# VISCAShield.net
KiCad netlist of a schematic drawn in EAGLE
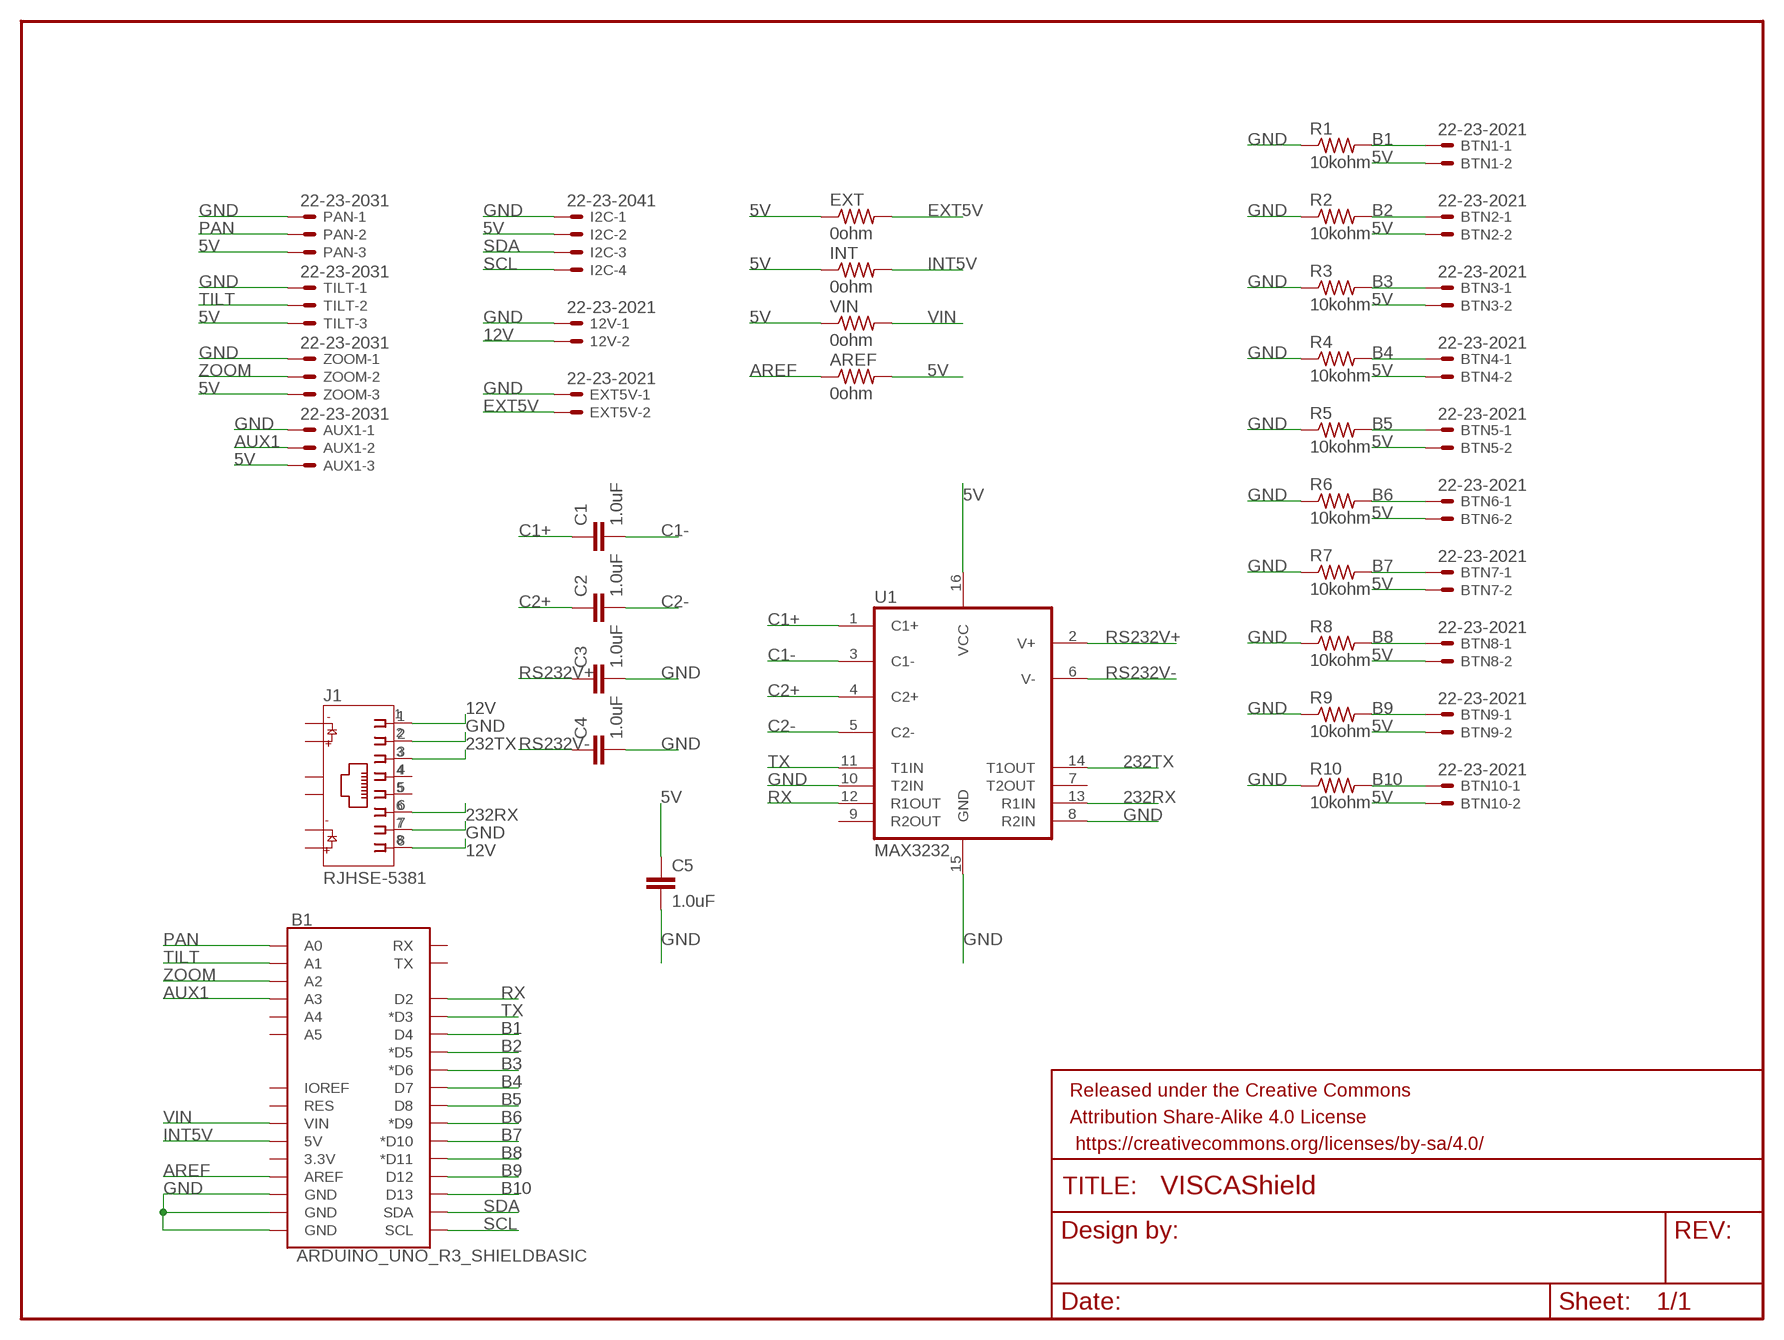
[diagram p0: schematic, sheet 1]

(export (version "E")
  (design (tool "Eeschema 10.0.6"))
  (components
    (comp (ref "12V")
      (value "22-23-2021")
      (footprint "eagle-import:22-23-2021")
      (fields (field (name "MF") "MOLEX"))
      (libsource (lib "eagle-import") (part "22-23-2021"))
    )
    (comp (ref "AREF")
      (value "0ohm")
      (footprint "eagle-import:0204V")
      (libsource (lib "eagle-import") (part "R-US_0204/2V"))
    )
    (comp (ref "AUX1")
      (value "22-23-2031")
      (footprint "eagle-import:22-23-2031")
      (fields (field (name "MF") "MOLEX"))
      (libsource (lib "eagle-import") (part "22-23-2031"))
    )
    (comp (ref "B1")
      (value "ARDUINO_UNO_R3_SHIELDBASIC")
      (footprint "eagle-import:UNO_R3_SHIELD")
      (libsource (lib "eagle-import") (part "ARDUINO_UNO_R3_SHIELDBASIC"))
    )
    (comp (ref "BTN1")
      (value "22-23-2021")
      (footprint "eagle-import:22-23-2021")
      (fields (field (name "MF") "MOLEX"))
      (libsource (lib "eagle-import") (part "22-23-2021"))
    )
    (comp (ref "BTN2")
      (value "22-23-2021")
      (footprint "eagle-import:22-23-2021")
      (fields (field (name "MF") "MOLEX"))
      (libsource (lib "eagle-import") (part "22-23-2021"))
    )
    (comp (ref "BTN3")
      (value "22-23-2021")
      (footprint "eagle-import:22-23-2021")
      (fields (field (name "MF") "MOLEX"))
      (libsource (lib "eagle-import") (part "22-23-2021"))
    )
    (comp (ref "BTN4")
      (value "22-23-2021")
      (footprint "eagle-import:22-23-2021")
      (fields (field (name "MF") "MOLEX"))
      (libsource (lib "eagle-import") (part "22-23-2021"))
    )
    (comp (ref "BTN5")
      (value "22-23-2021")
      (footprint "eagle-import:22-23-2021")
      (fields (field (name "MF") "MOLEX"))
      (libsource (lib "eagle-import") (part "22-23-2021"))
    )
    (comp (ref "BTN6")
      (value "22-23-2021")
      (footprint "eagle-import:22-23-2021")
      (fields (field (name "MF") "MOLEX"))
      (libsource (lib "eagle-import") (part "22-23-2021"))
    )
    (comp (ref "BTN7")
      (value "22-23-2021")
      (footprint "eagle-import:22-23-2021")
      (fields (field (name "MF") "MOLEX"))
      (libsource (lib "eagle-import") (part "22-23-2021"))
    )
    (comp (ref "BTN8")
      (value "22-23-2021")
      (footprint "eagle-import:22-23-2021")
      (fields (field (name "MF") "MOLEX"))
      (libsource (lib "eagle-import") (part "22-23-2021"))
    )
    (comp (ref "BTN9")
      (value "22-23-2021")
      (footprint "eagle-import:22-23-2021")
      (fields (field (name "MF") "MOLEX"))
      (libsource (lib "eagle-import") (part "22-23-2021"))
    )
    (comp (ref "BTN10")
      (value "22-23-2021")
      (footprint "eagle-import:22-23-2021")
      (fields (field (name "MF") "MOLEX"))
      (libsource (lib "eagle-import") (part "22-23-2021"))
    )
    (comp (ref "C1")
      (value "1.0uF")
      (footprint "eagle-import:0805")
      (libsource (lib "eagle-import") (part "1.0UF-0805-25V-(+80/-20%)"))
    )
    (comp (ref "C2")
      (value "1.0uF")
      (footprint "eagle-import:0805")
      (libsource (lib "eagle-import") (part "1.0UF-0805-25V-(+80/-20%)"))
    )
    (comp (ref "C3")
      (value "1.0uF")
      (footprint "eagle-import:0805")
      (libsource (lib "eagle-import") (part "1.0UF-0805-25V-(+80/-20%)"))
    )
    (comp (ref "C4")
      (value "1.0uF")
      (footprint "eagle-import:0805")
      (libsource (lib "eagle-import") (part "1.0UF-0805-25V-(+80/-20%)"))
    )
    (comp (ref "C5")
      (value "1.0uF")
      (footprint "eagle-import:0805")
      (libsource (lib "eagle-import") (part "1.0UF-0805-25V-(+80/-20%)"))
    )
    (comp (ref "EXT")
      (value "0ohm")
      (footprint "eagle-import:0204V")
      (libsource (lib "eagle-import") (part "R-US_0204/2V"))
    )
    (comp (ref "EXT5V")
      (value "22-23-2021")
      (footprint "eagle-import:22-23-2021")
      (fields (field (name "MF") "MOLEX"))
      (libsource (lib "eagle-import") (part "22-23-2021"))
    )
    (comp (ref "FRAME1")
      (value "FRAME-LETTERNO_PACKAGE")
      (footprint "eagle-import:DUMMY")
      (fields (field (name "DESIGNER") "Nobody"))
      (libsource (lib "eagle-import") (part "FRAME-LETTERNO_PACKAGE"))
    )
    (comp (ref "I2C")
      (value "22-23-2041")
      (footprint "eagle-import:22-23-2041")
      (fields (field (name "MF") "MOLEX"))
      (libsource (lib "eagle-import") (part "22-23-2041"))
    )
    (comp (ref "INT")
      (value "0ohm")
      (footprint "eagle-import:0204V")
      (libsource (lib "eagle-import") (part "R-US_0204/2V"))
    )
    (comp (ref "J1")
      (value "RJHSE-5381")
      (footprint "eagle-import:AMPHENOL_RJHSE-5381")
      (fields (field (name "MF") "Amphenol ICC"))
      (libsource (lib "eagle-import") (part "RJHSE-5381"))
    )
    (comp (ref "PAN")
      (value "22-23-2031")
      (footprint "eagle-import:22-23-2031")
      (fields (field (name "MF") "MOLEX"))
      (libsource (lib "eagle-import") (part "22-23-2031"))
    )
    (comp (ref "R1")
      (value "10kohm")
      (footprint "eagle-import:0204V")
      (libsource (lib "eagle-import") (part "R-US_0204/2V"))
    )
    (comp (ref "R2")
      (value "10kohm")
      (footprint "eagle-import:0204V")
      (libsource (lib "eagle-import") (part "R-US_0204/2V"))
    )
    (comp (ref "R3")
      (value "10kohm")
      (footprint "eagle-import:0204V")
      (libsource (lib "eagle-import") (part "R-US_0204/2V"))
    )
    (comp (ref "R4")
      (value "10kohm")
      (footprint "eagle-import:0204V")
      (libsource (lib "eagle-import") (part "R-US_0204/2V"))
    )
    (comp (ref "R5")
      (value "10kohm")
      (footprint "eagle-import:0204V")
      (libsource (lib "eagle-import") (part "R-US_0204/2V"))
    )
    (comp (ref "R6")
      (value "10kohm")
      (footprint "eagle-import:0204V")
      (libsource (lib "eagle-import") (part "R-US_0204/2V"))
    )
    (comp (ref "R7")
      (value "10kohm")
      (footprint "eagle-import:0204V")
      (libsource (lib "eagle-import") (part "R-US_0204/2V"))
    )
    (comp (ref "R8")
      (value "10kohm")
      (footprint "eagle-import:0204V")
      (libsource (lib "eagle-import") (part "R-US_0204/2V"))
    )
    (comp (ref "R9")
      (value "10kohm")
      (footprint "eagle-import:0204V")
      (libsource (lib "eagle-import") (part "R-US_0204/2V"))
    )
    (comp (ref "R10")
      (value "10kohm")
      (footprint "eagle-import:0204V")
      (libsource (lib "eagle-import") (part "R-US_0204/2V"))
    )
    (comp (ref "TILT")
      (value "22-23-2031")
      (footprint "eagle-import:22-23-2031")
      (fields (field (name "MF") "MOLEX"))
      (libsource (lib "eagle-import") (part "22-23-2031"))
    )
    (comp (ref "U1")
      (value "MAX3232")
      (footprint "eagle-import:SO16")
      (libsource (lib "eagle-import") (part "MAX2323SOIC16"))
    )
    (comp (ref "VIN")
      (value "0ohm")
      (footprint "eagle-import:0204V")
      (libsource (lib "eagle-import") (part "R-US_0204/2V"))
    )
    (comp (ref "ZOOM")
      (value "22-23-2031")
      (footprint "eagle-import:22-23-2031")
      (fields (field (name "MF") "MOLEX"))
      (libsource (lib "eagle-import") (part "22-23-2031"))
    )
  )
  (nets
    (net (code "1") (name "/5V") (class "Default")
      (node (ref "AREF") (pin "2") (pinfunction "2_2") (pintype "passive"))
      (node (ref "AUX1") (pin "3") (pinfunction "S_3") (pintype "passive"))
      (node (ref "BTN1") (pin "2") (pinfunction "S_2") (pintype "passive"))
      (node (ref "BTN10") (pin "2") (pinfunction "S_2") (pintype "passive"))
      (node (ref "BTN2") (pin "2") (pinfunction "S_2") (pintype "passive"))
      (node (ref "BTN3") (pin "2") (pinfunction "S_2") (pintype "passive"))
      (node (ref "BTN4") (pin "2") (pinfunction "S_2") (pintype "passive"))
      (node (ref "BTN5") (pin "2") (pinfunction "S_2") (pintype "passive"))
      (node (ref "BTN6") (pin "2") (pinfunction "S_2") (pintype "passive"))
      (node (ref "BTN7") (pin "2") (pinfunction "S_2") (pintype "passive"))
      (node (ref "BTN8") (pin "2") (pinfunction "S_2") (pintype "passive"))
      (node (ref "BTN9") (pin "2") (pinfunction "S_2") (pintype "passive"))
      (node (ref "C5") (pin "1") (pinfunction "1_1") (pintype "passive"))
      (node (ref "EXT") (pin "1") (pinfunction "1_1") (pintype "passive"))
      (node (ref "I2C") (pin "2") (pinfunction "S_2") (pintype "passive"))
      (node (ref "INT") (pin "1") (pinfunction "1_1") (pintype "passive"))
      (node (ref "PAN") (pin "3") (pinfunction "S_3") (pintype "passive"))
      (node (ref "TILT") (pin "3") (pinfunction "S_3") (pintype "passive"))
      (node (ref "U1") (pin "16") (pinfunction "VCC_16") (pintype "bidirectional"))
      (node (ref "VIN") (pin "1") (pinfunction "1_1") (pintype "passive"))
      (node (ref "ZOOM") (pin "3") (pinfunction "S_3") (pintype "passive"))
    )
    (net (code "2") (name "/12V") (class "Default")
      (node (ref "12V") (pin "2") (pinfunction "S_2") (pintype "passive"))
      (node (ref "J1") (pin "1") (pinfunction "1_1") (pintype "passive"))
      (node (ref "J1") (pin "8") (pinfunction "8_8") (pintype "passive"))
    )
    (net (code "3") (name "/232RX") (class "Default")
      (node (ref "J1") (pin "6") (pinfunction "6_6") (pintype "passive"))
      (node (ref "U1") (pin "13") (pinfunction "R1IN_13") (pintype "input"))
    )
    (net (code "4") (name "/232TX") (class "Default")
      (node (ref "J1") (pin "3") (pinfunction "3_3") (pintype "passive"))
      (node (ref "U1") (pin "14") (pinfunction "T1OUT_14") (pintype "output"))
    )
    (net (code "5") (name "/AREF") (class "Default")
      (node (ref "AREF") (pin "1") (pinfunction "1_1") (pintype "passive"))
      (node (ref "B1") (pin "AREF") (pinfunction "AREF_AREF") (pintype "bidirectional"))
    )
    (net (code "6") (name "/AUX1") (class "Default")
      (node (ref "AUX1") (pin "2") (pinfunction "S_2") (pintype "passive"))
      (node (ref "B1") (pin "A3") (pinfunction "A3_A3") (pintype "bidirectional"))
    )
    (net (code "7") (name "/B1") (class "Default")
      (node (ref "B1") (pin "D4") (pinfunction "D4_D4") (pintype "bidirectional"))
      (node (ref "BTN1") (pin "1") (pinfunction "S_1") (pintype "passive"))
      (node (ref "R1") (pin "2") (pinfunction "2_2") (pintype "passive"))
    )
    (net (code "8") (name "/B2") (class "Default")
      (node (ref "B1") (pin "D5") (pinfunction "*D5_D5") (pintype "bidirectional"))
      (node (ref "BTN2") (pin "1") (pinfunction "S_1") (pintype "passive"))
      (node (ref "R2") (pin "2") (pinfunction "2_2") (pintype "passive"))
    )
    (net (code "9") (name "/B3") (class "Default")
      (node (ref "B1") (pin "D6") (pinfunction "*D6_D6") (pintype "bidirectional"))
      (node (ref "BTN3") (pin "1") (pinfunction "S_1") (pintype "passive"))
      (node (ref "R3") (pin "2") (pinfunction "2_2") (pintype "passive"))
    )
    (net (code "10") (name "/B4") (class "Default")
      (node (ref "B1") (pin "D7") (pinfunction "D7_D7") (pintype "bidirectional"))
      (node (ref "BTN4") (pin "1") (pinfunction "S_1") (pintype "passive"))
      (node (ref "R4") (pin "2") (pinfunction "2_2") (pintype "passive"))
    )
    (net (code "11") (name "/B5") (class "Default")
      (node (ref "B1") (pin "D8") (pinfunction "D8_D8") (pintype "bidirectional"))
      (node (ref "BTN5") (pin "1") (pinfunction "S_1") (pintype "passive"))
      (node (ref "R5") (pin "2") (pinfunction "2_2") (pintype "passive"))
    )
    (net (code "12") (name "/B6") (class "Default")
      (node (ref "B1") (pin "D9") (pinfunction "*D9_D9") (pintype "bidirectional"))
      (node (ref "BTN6") (pin "1") (pinfunction "S_1") (pintype "passive"))
      (node (ref "R6") (pin "2") (pinfunction "2_2") (pintype "passive"))
    )
    (net (code "13") (name "/B7") (class "Default")
      (node (ref "B1") (pin "D10") (pinfunction "*D10_D10") (pintype "bidirectional"))
      (node (ref "BTN7") (pin "1") (pinfunction "S_1") (pintype "passive"))
      (node (ref "R7") (pin "2") (pinfunction "2_2") (pintype "passive"))
    )
    (net (code "14") (name "/B8") (class "Default")
      (node (ref "B1") (pin "D11") (pinfunction "*D11_D11") (pintype "bidirectional"))
      (node (ref "BTN8") (pin "1") (pinfunction "S_1") (pintype "passive"))
      (node (ref "R8") (pin "2") (pinfunction "2_2") (pintype "passive"))
    )
    (net (code "15") (name "/B9") (class "Default")
      (node (ref "B1") (pin "D12") (pinfunction "D12_D12") (pintype "bidirectional"))
      (node (ref "BTN9") (pin "1") (pinfunction "S_1") (pintype "passive"))
      (node (ref "R9") (pin "2") (pinfunction "2_2") (pintype "passive"))
    )
    (net (code "16") (name "/B10") (class "Default")
      (node (ref "B1") (pin "D13") (pinfunction "D13_D13") (pintype "bidirectional"))
      (node (ref "BTN10") (pin "1") (pinfunction "S_1") (pintype "passive"))
      (node (ref "R10") (pin "2") (pinfunction "2_2") (pintype "passive"))
    )
    (net (code "17") (name "/C1+") (class "Default")
      (node (ref "C1") (pin "1") (pinfunction "1_1") (pintype "passive"))
      (node (ref "U1") (pin "1") (pinfunction "C1+_1") (pintype "bidirectional"))
    )
    (net (code "18") (name "/C1-") (class "Default")
      (node (ref "C1") (pin "2") (pinfunction "2_2") (pintype "passive"))
      (node (ref "U1") (pin "3") (pinfunction "C1-_3") (pintype "bidirectional"))
    )
    (net (code "19") (name "/C2+") (class "Default")
      (node (ref "C2") (pin "1") (pinfunction "1_1") (pintype "passive"))
      (node (ref "U1") (pin "4") (pinfunction "C2+_4") (pintype "bidirectional"))
    )
    (net (code "20") (name "/C2-") (class "Default")
      (node (ref "C2") (pin "2") (pinfunction "2_2") (pintype "passive"))
      (node (ref "U1") (pin "5") (pinfunction "C2-_5") (pintype "bidirectional"))
    )
    (net (code "21") (name "/EXT5V") (class "Default")
      (node (ref "EXT") (pin "2") (pinfunction "2_2") (pintype "passive"))
      (node (ref "EXT5V") (pin "2") (pinfunction "S_2") (pintype "passive"))
    )
    (net (code "22") (name "/GND") (class "Default")
      (node (ref "12V") (pin "1") (pinfunction "S_1") (pintype "passive"))
      (node (ref "AUX1") (pin "1") (pinfunction "S_1") (pintype "passive"))
      (node (ref "B1") (pin "GND@0") (pinfunction "GND_GND@0") (pintype "bidirectional"))
      (node (ref "B1") (pin "GND@1") (pinfunction "GND_GND@1") (pintype "bidirectional"))
      (node (ref "B1") (pin "GND@2") (pinfunction "GND_GND@2") (pintype "bidirectional"))
      (node (ref "C3") (pin "2") (pinfunction "2_2") (pintype "passive"))
      (node (ref "C4") (pin "2") (pinfunction "2_2") (pintype "passive"))
      (node (ref "C5") (pin "2") (pinfunction "2_2") (pintype "passive"))
      (node (ref "EXT5V") (pin "1") (pinfunction "S_1") (pintype "passive"))
      (node (ref "I2C") (pin "1") (pinfunction "S_1") (pintype "passive"))
      (node (ref "J1") (pin "2") (pinfunction "2_2") (pintype "passive"))
      (node (ref "J1") (pin "7") (pinfunction "7_7") (pintype "passive"))
      (node (ref "PAN") (pin "1") (pinfunction "S_1") (pintype "passive"))
      (node (ref "R1") (pin "1") (pinfunction "1_1") (pintype "passive"))
      (node (ref "R10") (pin "1") (pinfunction "1_1") (pintype "passive"))
      (node (ref "R2") (pin "1") (pinfunction "1_1") (pintype "passive"))
      (node (ref "R3") (pin "1") (pinfunction "1_1") (pintype "passive"))
      (node (ref "R4") (pin "1") (pinfunction "1_1") (pintype "passive"))
      (node (ref "R5") (pin "1") (pinfunction "1_1") (pintype "passive"))
      (node (ref "R6") (pin "1") (pinfunction "1_1") (pintype "passive"))
      (node (ref "R7") (pin "1") (pinfunction "1_1") (pintype "passive"))
      (node (ref "R8") (pin "1") (pinfunction "1_1") (pintype "passive"))
      (node (ref "R9") (pin "1") (pinfunction "1_1") (pintype "passive"))
      (node (ref "TILT") (pin "1") (pinfunction "S_1") (pintype "passive"))
      (node (ref "U1") (pin "10") (pinfunction "T2IN_10") (pintype "input"))
      (node (ref "U1") (pin "15") (pinfunction "GND_15") (pintype "bidirectional"))
      (node (ref "U1") (pin "8") (pinfunction "R2IN_8") (pintype "input"))
      (node (ref "ZOOM") (pin "1") (pinfunction "S_1") (pintype "passive"))
    )
    (net (code "23") (name "/INT5V") (class "Default")
      (node (ref "B1") (pin "5V") (pinfunction "5V_5V") (pintype "bidirectional"))
      (node (ref "INT") (pin "2") (pinfunction "2_2") (pintype "passive"))
    )
    (net (code "24") (name "/PAN") (class "Default")
      (node (ref "B1") (pin "A0") (pinfunction "A0_A0") (pintype "bidirectional"))
      (node (ref "PAN") (pin "2") (pinfunction "S_2") (pintype "passive"))
    )
    (net (code "25") (name "/RS232V+") (class "Default")
      (node (ref "C3") (pin "1") (pinfunction "1_1") (pintype "passive"))
      (node (ref "U1") (pin "2") (pinfunction "V+_2") (pintype "bidirectional"))
    )
    (net (code "26") (name "/RS232V-") (class "Default")
      (node (ref "C4") (pin "1") (pinfunction "1_1") (pintype "passive"))
      (node (ref "U1") (pin "6") (pinfunction "V-_6") (pintype "bidirectional"))
    )
    (net (code "27") (name "/RX") (class "Default")
      (node (ref "B1") (pin "D2") (pinfunction "D2_D2") (pintype "bidirectional"))
      (node (ref "U1") (pin "12") (pinfunction "R1OUT_12") (pintype "output"))
    )
    (net (code "28") (name "/SCL") (class "Default")
      (node (ref "B1") (pin "SCL") (pinfunction "SCL_SCL") (pintype "bidirectional"))
      (node (ref "I2C") (pin "4") (pinfunction "S_4") (pintype "passive"))
    )
    (net (code "29") (name "/SDA") (class "Default")
      (node (ref "B1") (pin "SDA") (pinfunction "SDA_SDA") (pintype "bidirectional"))
      (node (ref "I2C") (pin "3") (pinfunction "S_3") (pintype "passive"))
    )
    (net (code "30") (name "/TILT") (class "Default")
      (node (ref "B1") (pin "A1") (pinfunction "A1_A1") (pintype "bidirectional"))
      (node (ref "TILT") (pin "2") (pinfunction "S_2") (pintype "passive"))
    )
    (net (code "31") (name "/TX") (class "Default")
      (node (ref "B1") (pin "D3") (pinfunction "*D3_D3") (pintype "bidirectional"))
      (node (ref "U1") (pin "11") (pinfunction "T1IN_11") (pintype "input"))
    )
    (net (code "32") (name "/VIN") (class "Default")
      (node (ref "B1") (pin "VIN") (pinfunction "VIN_VIN") (pintype "bidirectional"))
      (node (ref "VIN") (pin "2") (pinfunction "2_2") (pintype "passive"))
    )
    (net (code "33") (name "/ZOOM") (class "Default")
      (node (ref "B1") (pin "A2") (pinfunction "A2_A2") (pintype "bidirectional"))
      (node (ref "ZOOM") (pin "2") (pinfunction "S_2") (pintype "passive"))
    )
    (net (code "34") (name "unconnected-(B1-Pad3.3V)") (class "Default")
      (node (ref "B1") (pin "3.3V") (pinfunction "3.3V_3.3V") (pintype "bidirectional"))
    )
    (net (code "35") (name "unconnected-(B1-PadA4)") (class "Default")
      (node (ref "B1") (pin "A4") (pinfunction "A4_A4") (pintype "bidirectional"))
    )
    (net (code "36") (name "unconnected-(B1-PadA5)") (class "Default")
      (node (ref "B1") (pin "A5") (pinfunction "A5_A5") (pintype "bidirectional"))
    )
    (net (code "37") (name "unconnected-(B1-PadIOREF)") (class "Default")
      (node (ref "B1") (pin "IOREF") (pinfunction "IOREF_IOREF") (pintype "bidirectional"))
    )
    (net (code "38") (name "unconnected-(B1-PadRES)") (class "Default")
      (node (ref "B1") (pin "RES") (pinfunction "RES_RES") (pintype "bidirectional"))
    )
    (net (code "39") (name "unconnected-(B1-PadRX)") (class "Default")
      (node (ref "B1") (pin "RX") (pinfunction "RX_RX") (pintype "bidirectional"))
    )
    (net (code "40") (name "unconnected-(B1-PadTX)") (class "Default")
      (node (ref "B1") (pin "TX") (pinfunction "TX_TX") (pintype "bidirectional"))
    )
    (net (code "41") (name "unconnected-(J1-Pad4)") (class "Default")
      (node (ref "J1") (pin "4") (pinfunction "4_4") (pintype "passive"))
    )
    (net (code "42") (name "unconnected-(J1-Pad5)") (class "Default")
      (node (ref "J1") (pin "5") (pinfunction "5_5") (pintype "passive"))
    )
    (net (code "43") (name "unconnected-(J1-Pad9)") (class "Default")
      (node (ref "J1") (pin "9") (pinfunction "9_9") (pintype "passive"))
    )
    (net (code "44") (name "unconnected-(J1-Pad10)") (class "Default")
      (node (ref "J1") (pin "10") (pinfunction "10_10") (pintype "passive"))
    )
    (net (code "45") (name "unconnected-(J1-Pad11)") (class "Default")
      (node (ref "J1") (pin "11") (pinfunction "11_11") (pintype "passive"))
    )
    (net (code "46") (name "unconnected-(J1-Pad12)") (class "Default")
      (node (ref "J1") (pin "12") (pinfunction "12_12") (pintype "passive"))
    )
    (net (code "47") (name "unconnected-(J1-PadS1)") (class "Default")
      (node (ref "J1") (pin "S1") (pinfunction "S1_S1") (pintype "passive"))
    )
    (net (code "48") (name "unconnected-(J1-PadS2)") (class "Default")
      (node (ref "J1") (pin "S2") (pinfunction "S2_S2") (pintype "passive"))
    )
    (net (code "49") (name "unconnected-(U1-R2OUT-Pad9)") (class "Default")
      (node (ref "U1") (pin "9") (pinfunction "R2OUT_9") (pintype "output"))
    )
    (net (code "50") (name "unconnected-(U1-T2OUT-Pad7)") (class "Default")
      (node (ref "U1") (pin "7") (pinfunction "T2OUT_7") (pintype "output"))
    )
  )
)
